# UI_Panel.net
KiCad netlist of a schematic drawn in Altium Designer
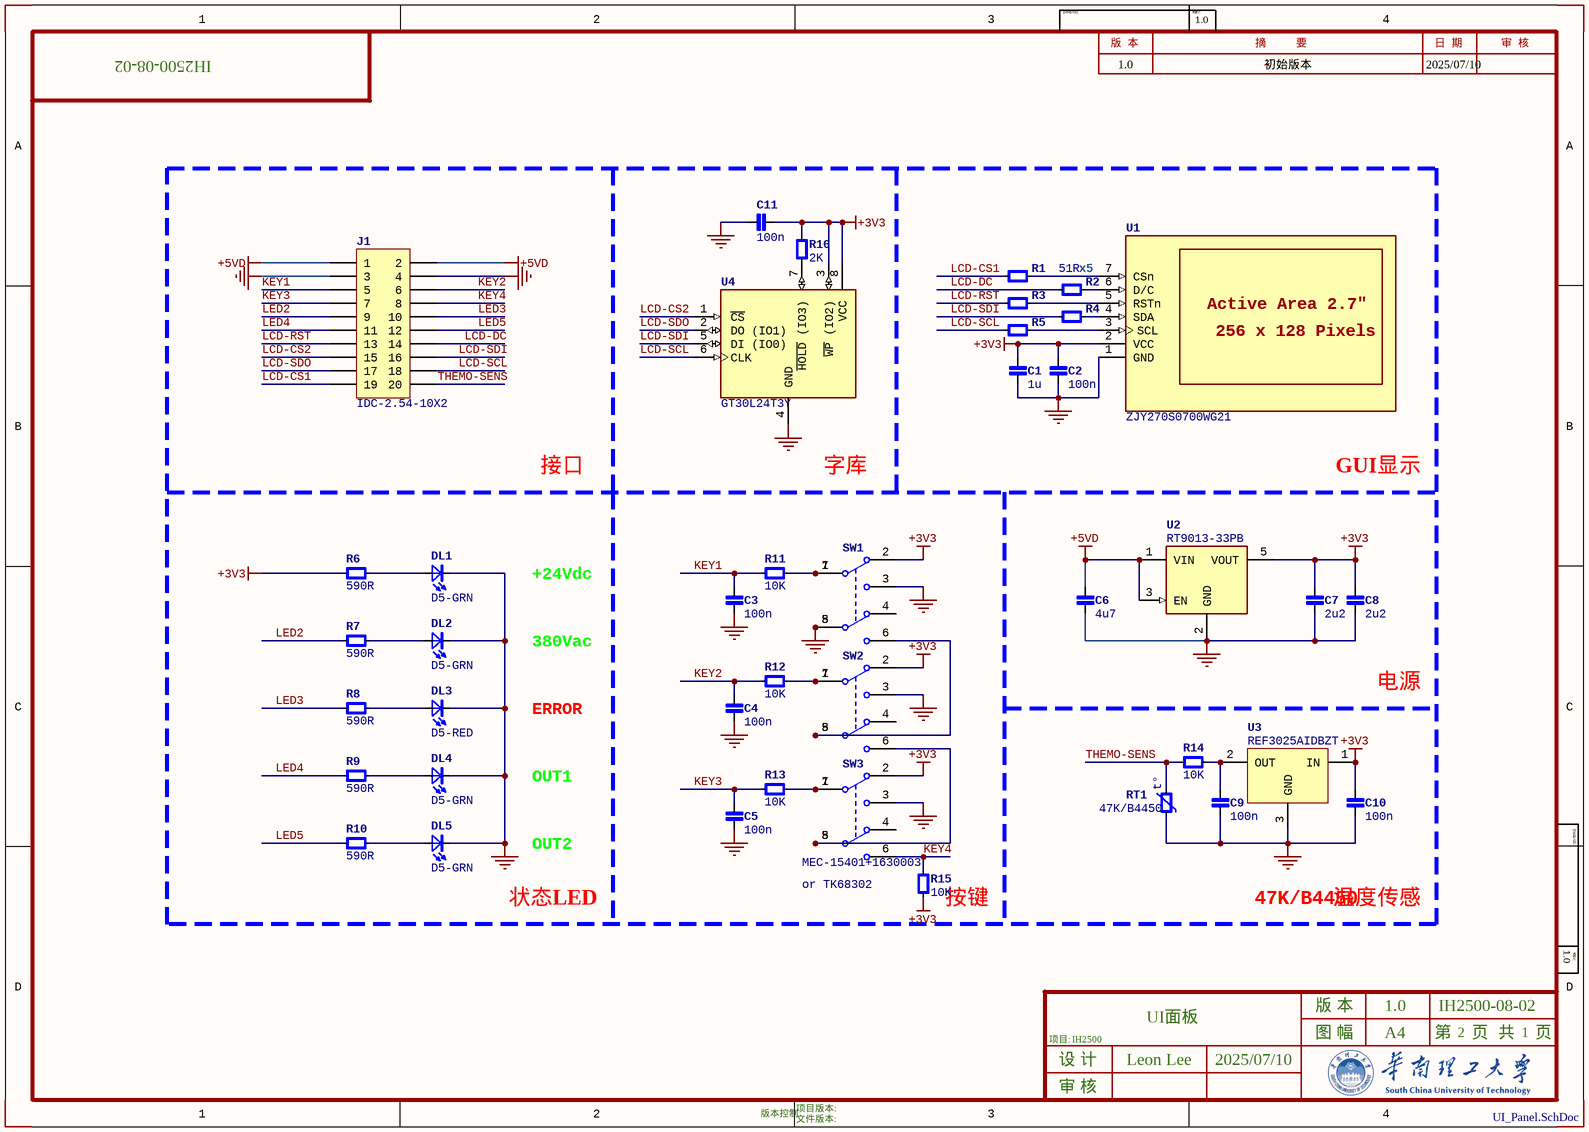
[diagram p0: UI_Panel.SchDoc]

(export (version "E")
  (design (tool "Eeschema 10.0.6"))
  (components
    (comp (ref "C1") (value "1u") (footprint "CAPC0805N") (libsource (lib "User_leo") (part "CAPACITOR(S)")))
    (comp (ref "C2")
      (value "100n")
      (footprint "CAPC0805N")
      (libsource (lib "User_leo") (part "CAPACITOR(S)"))
    )
    (comp (ref "C3")
      (value "100n")
      (footprint "CAPC0805N")
      (libsource (lib "User_leo") (part "CAPACITOR(S)"))
    )
    (comp (ref "C4")
      (value "100n")
      (footprint "CAPC0805N")
      (libsource (lib "User_leo") (part "CAPACITOR(S)"))
    )
    (comp (ref "C5")
      (value "100n")
      (footprint "CAPC0805N")
      (libsource (lib "User_leo") (part "CAPACITOR(S)"))
    )
    (comp (ref "C6") (value "4u7") (footprint "CAPC0805N") (libsource (lib "*") (part "CAPACITOR(S)")))
    (comp (ref "C7") (value "2u2") (footprint "CAPC0805N") (libsource (lib "User_leo") (part "CAPACITOR(S)")))
    (comp (ref "C8") (value "2u2") (footprint "CAPC0805N") (libsource (lib "User_leo") (part "CAPACITOR(S)")))
    (comp (ref "C9")
      (value "100n")
      (footprint "CAPC0805N")
      (libsource (lib "User_leo") (part "CAPACITOR(S)"))
    )
    (comp (ref "C10")
      (value "100n")
      (footprint "CAPC0805N")
      (libsource (lib "User_leo") (part "CAPACITOR(S)"))
    )
    (comp (ref "C11")
      (value "100n")
      (footprint "CAPC0805N")
      (libsource (lib "User_leo") (part "CAPACITOR(S)"))
    )
    (comp (ref "DL1")
      (value "D5-GRN")
      (footprint "LED-D5-GRN")
      (description "发光二极管")
      (libsource (lib "User_leo") (part "LED(S)"))
    )
    (comp (ref "DL2")
      (value "D5-GRN")
      (footprint "LED-D5-GRN")
      (description "发光二极管")
      (libsource (lib "User_leo") (part "LED(S)"))
    )
    (comp (ref "DL3")
      (value "D5-RED")
      (footprint "LED-D5-RED")
      (description "发光二极管")
      (libsource (lib "User_leo") (part "LED(S)"))
    )
    (comp (ref "DL4")
      (value "D5-GRN")
      (footprint "LED-D5-GRN")
      (description "发光二极管")
      (libsource (lib "User_leo") (part "LED(S)"))
    )
    (comp (ref "DL5")
      (value "D5-GRN")
      (footprint "LED-D5-GRN")
      (description "发光二极管")
      (libsource (lib "User_leo") (part "LED(S)"))
    )
    (comp (ref "J1")
      (value "IDC-2.54-10X2")
      (footprint "IDC2.54-V20A")
      (description "Header, 10-Pin, Dual row")
      (fields (field (name "PUBLISHER") "Altium Limited"))
      (libsource (lib "Miscellaneous Connectors") (part "Header 10X2"))
    )
    (comp (ref "R1")
      (value "51R")
      (footprint "RESC0805N")
      (description "电阻")
      (libsource (lib "User_leo") (part "RESISTOR(S)"))
    )
    (comp (ref "R2")
      (value "51R")
      (footprint "RESC0805N")
      (description "电阻")
      (libsource (lib "User_leo") (part "RESISTOR(S)"))
    )
    (comp (ref "R3")
      (value "51R")
      (footprint "RESC0805N")
      (description "电阻")
      (libsource (lib "User_leo") (part "RESISTOR(S)"))
    )
    (comp (ref "R4")
      (value "51R")
      (footprint "RESC0805N")
      (description "电阻")
      (libsource (lib "User_leo") (part "RESISTOR(S)"))
    )
    (comp (ref "R5")
      (value "51R")
      (footprint "RESC0805N")
      (description "电阻")
      (libsource (lib "User_leo") (part "RESISTOR(S)"))
    )
    (comp (ref "R6")
      (value "590R")
      (footprint "RESC0805N")
      (description "电阻")
      (libsource (lib "User_leo") (part "RESISTOR(S)"))
    )
    (comp (ref "R7")
      (value "590R")
      (footprint "RESC0805N")
      (description "电阻")
      (libsource (lib "User_leo") (part "RESISTOR(S)"))
    )
    (comp (ref "R8")
      (value "590R")
      (footprint "RESC0805N")
      (description "电阻")
      (libsource (lib "User_leo") (part "RESISTOR(S)"))
    )
    (comp (ref "R9")
      (value "590R")
      (footprint "RESC0805N")
      (description "电阻")
      (libsource (lib "User_leo") (part "RESISTOR(S)"))
    )
    (comp (ref "R10")
      (value "590R")
      (footprint "RESC0805N")
      (description "电阻")
      (libsource (lib "User_leo") (part "RESISTOR(S)"))
    )
    (comp (ref "R11")
      (value "10K")
      (footprint "RESC0805N")
      (description "电阻")
      (libsource (lib "User_leo") (part "RESISTOR(S)"))
    )
    (comp (ref "R12")
      (value "10K")
      (footprint "RESC0805N")
      (description "电阻")
      (libsource (lib "User_leo") (part "RESISTOR(S)"))
    )
    (comp (ref "R13")
      (value "10K")
      (footprint "RESC0805N")
      (description "电阻")
      (libsource (lib "User_leo") (part "RESISTOR(S)"))
    )
    (comp (ref "R14") (value "10K") (footprint "RESC0805N") (libsource (lib "*") (part "RESISTOR(S)")))
    (comp (ref "R15")
      (value "10K")
      (footprint "RESC0805N")
      (description "电阻")
      (libsource (lib "User_leo") (part "RESISTOR(S)"))
    )
    (comp (ref "R16") (value "2K") (footprint "RESC0805N") (libsource (lib "*") (part "RESISTOR(S)")))
    (comp (ref "RT1")
      (value "47K/B4450")
      (footprint "RESC0805N")
      (description "热敏电阻")
      (libsource (lib "User_leo") (part "RESISTOR(S) Thermal"))
    )
    (comp (ref "SW1")
      (value "MEC-15401+1630003")
      (footprint "SW-MEC-15xxx")
      (description "Switch")
      (fields (field (name "PUBLISHER") "Altium Limited"))
      (libsource (lib "Miscellaneous Devices") (part "SW DPDT"))
    )
    (comp (ref "SW2")
      (value "MEC-15401+1630003")
      (footprint "SW-MEC-15xxx")
      (description "Switch")
      (fields (field (name "PUBLISHER") "Altium Limited"))
      (libsource (lib "Miscellaneous Devices") (part "SW DPDT"))
    )
    (comp (ref "SW3")
      (value "MEC-15401+1630003")
      (footprint "SW-MEC-15xxx")
      (description "Switch")
      (fields (field (name "PUBLISHER") "Altium Limited"))
      (libsource (lib "Miscellaneous Devices") (part "SW DPDT"))
    )
    (comp (ref "U1")
      (value "ZJY270S0700WG21")
      (footprint "OLED-2.7-85x50")
      (description "中景园，ZJY270S0700YG21/WG21 OLED显示模组，256x128像素，16级灰度，SSD1363控制器，YG-黄色，WG-白色")
      (libsource (lib "User_leo") (part "OLED-ZJY270S0700"))
    )
    (comp (ref "U2")
      (value "RT9013-33PB")
      (footprint "SOT23-5_N")
      (description "500mA, Low Dropout, Low Noise Ultra-Fast Without Bypass Capacitor CMOS LDO Regulator")
      (libsource (lib "User_leo") (part "RT9013-xxPB"))
    )
    (comp (ref "U3")
      (value "REF3025AIDBZT")
      (footprint "DBZ0003A_N")
      (fields (field (name "MANUFACTURER") "Texas Instruments"))
      (libsource (lib "Altium Content Vault") (part "TI-REF3025DBZ3"))
    )
    (comp (ref "U4")
      (value "GT30L24T3Y")
      (footprint "SOP127P780-8N")
      (libsource (lib "User_leo") (part "WINB-W25Q40CL-SOIC-8"))
    )
  )
  (nets
    (net (code "1") (name "+3V3") (class "Default")
      (node (ref "C1") (pin "1") (pinfunction "1_1") (pintype "passive"))
      (node (ref "C10") (pin "1") (pinfunction "1_1") (pintype "passive"))
      (node (ref "C11") (pin "2") (pinfunction "2_2") (pintype "passive"))
      (node (ref "C2") (pin "1") (pinfunction "1_1") (pintype "passive"))
      (node (ref "C7") (pin "1") (pinfunction "1_1") (pintype "passive"))
      (node (ref "C8") (pin "1") (pinfunction "1_1") (pintype "passive"))
      (node (ref "R15") (pin "1") (pinfunction "1_1") (pintype "passive"))
      (node (ref "R16") (pin "1") (pinfunction "1_1") (pintype "passive"))
      (node (ref "R6") (pin "1") (pinfunction "1_1") (pintype "passive"))
      (node (ref "SW1") (pin "2") (pinfunction "NC1_2") (pintype "passive"))
      (node (ref "SW2") (pin "2") (pinfunction "NC1_2") (pintype "passive"))
      (node (ref "SW3") (pin "2") (pinfunction "NC1_2") (pintype "passive"))
      (node (ref "U1") (pin "2") (pinfunction "VCC_2") (pintype "power_in"))
      (node (ref "U2") (pin "5") (pinfunction "VOUT_5") (pintype "passive"))
      (node (ref "U3") (pin "1") (pinfunction "IN_1") (pintype "power_in"))
      (node (ref "U4") (pin "3") (pinfunction "~{WP}_(IO2)_3") (pintype "bidirectional"))
      (node (ref "U4") (pin "8") (pinfunction "VCC_8") (pintype "power_in"))
    )
    (net (code "2") (name "+5VD") (class "Default")
      (node (ref "C6") (pin "1") (pinfunction "1_1") (pintype "passive"))
      (node (ref "J1") (pin "1") (pinfunction "1_1") (pintype "passive"))
      (node (ref "J1") (pin "2") (pinfunction "2_2") (pintype "passive"))
      (node (ref "U2") (pin "1") (pinfunction "VIN_1") (pintype "passive"))
      (node (ref "U2") (pin "3") (pinfunction "EN_3") (pintype "input"))
    )
    (net (code "3") (name "/KEY1") (class "Default")
      (node (ref "C3") (pin "1") (pinfunction "1_1") (pintype "passive"))
      (node (ref "J1") (pin "5") (pinfunction "5_5") (pintype "passive"))
      (node (ref "R11") (pin "1") (pinfunction "1_1") (pintype "passive"))
    )
    (net (code "4") (name "/KEY2") (class "Default")
      (node (ref "C4") (pin "1") (pinfunction "1_1") (pintype "passive"))
      (node (ref "J1") (pin "6") (pinfunction "6_6") (pintype "passive"))
      (node (ref "R12") (pin "1") (pinfunction "1_1") (pintype "passive"))
    )
    (net (code "5") (name "/KEY3") (class "Default")
      (node (ref "C5") (pin "1") (pinfunction "1_1") (pintype "passive"))
      (node (ref "J1") (pin "7") (pinfunction "7_7") (pintype "passive"))
      (node (ref "R13") (pin "1") (pinfunction "1_1") (pintype "passive"))
    )
    (net (code "6") (name "/KEY4") (class "Default")
      (node (ref "J1") (pin "8") (pinfunction "8_8") (pintype "passive"))
      (node (ref "R15") (pin "2") (pinfunction "2_2") (pintype "passive"))
      (node (ref "SW3") (pin "6") (pinfunction "NO2_6") (pintype "passive"))
    )
    (net (code "7") (name "/LCD-CS1") (class "Default")
      (node (ref "J1") (pin "19") (pinfunction "19_19") (pintype "passive"))
      (node (ref "R1") (pin "1") (pinfunction "1_1") (pintype "passive"))
    )
    (net (code "8") (name "/LCD-CS2") (class "Default")
      (node (ref "J1") (pin "15") (pinfunction "15_15") (pintype "passive"))
      (node (ref "U4") (pin "1") (pinfunction "~{CS}_1") (pintype "input"))
    )
    (net (code "9") (name "/LCD-DC") (class "Default")
      (node (ref "J1") (pin "14") (pinfunction "14_14") (pintype "passive"))
      (node (ref "R2") (pin "1") (pinfunction "1_1") (pintype "passive"))
    )
    (net (code "10") (name "/LCD-RST") (class "Default")
      (node (ref "J1") (pin "13") (pinfunction "13_13") (pintype "passive"))
      (node (ref "R3") (pin "1") (pinfunction "1_1") (pintype "passive"))
    )
    (net (code "11") (name "/LCD-SCL") (class "Default")
      (node (ref "J1") (pin "18") (pinfunction "18_18") (pintype "passive"))
      (node (ref "R5") (pin "1") (pinfunction "1_1") (pintype "passive"))
      (node (ref "U4") (pin "6") (pinfunction "CLK_6") (pintype "input"))
    )
    (net (code "12") (name "/LCD-SDI") (class "Default")
      (node (ref "J1") (pin "16") (pinfunction "16_16") (pintype "passive"))
      (node (ref "R4") (pin "1") (pinfunction "1_1") (pintype "passive"))
      (node (ref "U4") (pin "5") (pinfunction "DI_(IO0)_5") (pintype "bidirectional"))
    )
    (net (code "13") (name "/LCD-SDO") (class "Default")
      (node (ref "J1") (pin "17") (pinfunction "17_17") (pintype "passive"))
      (node (ref "U4") (pin "2") (pinfunction "DO_(IO1)_2") (pintype "bidirectional"))
    )
    (net (code "14") (name "/LED2") (class "Default")
      (node (ref "J1") (pin "9") (pinfunction "9_9") (pintype "passive"))
      (node (ref "R7") (pin "1") (pinfunction "1_1") (pintype "passive"))
    )
    (net (code "15") (name "/LED3") (class "Default")
      (node (ref "J1") (pin "10") (pinfunction "10_10") (pintype "passive"))
      (node (ref "R8") (pin "1") (pinfunction "1_1") (pintype "passive"))
    )
    (net (code "16") (name "/LED4") (class "Default")
      (node (ref "J1") (pin "11") (pinfunction "11_11") (pintype "passive"))
      (node (ref "R9") (pin "1") (pinfunction "1_1") (pintype "passive"))
    )
    (net (code "17") (name "/LED5") (class "Default")
      (node (ref "J1") (pin "12") (pinfunction "12_12") (pintype "passive"))
      (node (ref "R10") (pin "1") (pinfunction "1_1") (pintype "passive"))
    )
    (net (code "18") (name "/THEMO-SENS") (class "Default")
      (node (ref "J1") (pin "20") (pinfunction "20_20") (pintype "passive"))
      (node (ref "R14") (pin "2") (pinfunction "2_2") (pintype "passive"))
      (node (ref "RT1") (pin "2") (pinfunction "2_2") (pintype "passive"))
    )
    (net (code "19") (name "GND") (class "Default")
      (node (ref "C1") (pin "2") (pinfunction "2_2") (pintype "passive"))
      (node (ref "C10") (pin "2") (pinfunction "2_2") (pintype "passive"))
      (node (ref "C11") (pin "1") (pinfunction "1_1") (pintype "passive"))
      (node (ref "C2") (pin "2") (pinfunction "2_2") (pintype "passive"))
      (node (ref "C3") (pin "2") (pinfunction "2_2") (pintype "passive"))
      (node (ref "C4") (pin "2") (pinfunction "2_2") (pintype "passive"))
      (node (ref "C5") (pin "2") (pinfunction "2_2") (pintype "passive"))
      (node (ref "C6") (pin "2") (pinfunction "2_2") (pintype "passive"))
      (node (ref "C7") (pin "2") (pinfunction "2_2") (pintype "passive"))
      (node (ref "C8") (pin "2") (pinfunction "2_2") (pintype "passive"))
      (node (ref "C9") (pin "2") (pinfunction "2_2") (pintype "passive"))
      (node (ref "DL1") (pin "2") (pinfunction "K_2") (pintype "passive"))
      (node (ref "DL2") (pin "2") (pinfunction "K_2") (pintype "passive"))
      (node (ref "DL3") (pin "2") (pinfunction "K_2") (pintype "passive"))
      (node (ref "DL4") (pin "2") (pinfunction "K_2") (pintype "passive"))
      (node (ref "DL5") (pin "2") (pinfunction "K_2") (pintype "passive"))
      (node (ref "J1") (pin "3") (pinfunction "3_3") (pintype "passive"))
      (node (ref "J1") (pin "4") (pinfunction "4_4") (pintype "passive"))
      (node (ref "RT1") (pin "1") (pinfunction "1_1") (pintype "passive"))
      (node (ref "SW1") (pin "3") (pinfunction "NO1_3") (pintype "passive"))
      (node (ref "SW1") (pin "5") (pinfunction "COMMON2_5") (pintype "passive"))
      (node (ref "SW1") (pin "8") (pinfunction "COM2_8") (pintype "passive"))
      (node (ref "SW2") (pin "3") (pinfunction "NO1_3") (pintype "passive"))
      (node (ref "SW3") (pin "3") (pinfunction "NO1_3") (pintype "passive"))
      (node (ref "U1") (pin "1") (pinfunction "GND_1") (pintype "power_in"))
      (node (ref "U2") (pin "2") (pinfunction "GND_2") (pintype "passive"))
      (node (ref "U3") (pin "3") (pinfunction "GND_3") (pintype "power_in"))
      (node (ref "U4") (pin "4") (pinfunction "GND_4") (pintype "power_in"))
    )
    (net (code "20") (name "Net-(DL1-A)") (class "Default")
      (node (ref "DL1") (pin "1") (pinfunction "A_1") (pintype "passive"))
      (node (ref "R6") (pin "2") (pinfunction "2_2") (pintype "passive"))
    )
    (net (code "21") (name "Net-(DL2-A)") (class "Default")
      (node (ref "DL2") (pin "1") (pinfunction "A_1") (pintype "passive"))
      (node (ref "R7") (pin "2") (pinfunction "2_2") (pintype "passive"))
    )
    (net (code "22") (name "Net-(DL3-A)") (class "Default")
      (node (ref "DL3") (pin "1") (pinfunction "A_1") (pintype "passive"))
      (node (ref "R8") (pin "2") (pinfunction "2_2") (pintype "passive"))
    )
    (net (code "23") (name "Net-(DL4-A)") (class "Default")
      (node (ref "DL4") (pin "1") (pinfunction "A_1") (pintype "passive"))
      (node (ref "R9") (pin "2") (pinfunction "2_2") (pintype "passive"))
    )
    (net (code "24") (name "Net-(DL5-A)") (class "Default")
      (node (ref "DL5") (pin "1") (pinfunction "A_1") (pintype "passive"))
      (node (ref "R10") (pin "2") (pinfunction "2_2") (pintype "passive"))
    )
    (net (code "25") (name "Net-(SW1-COM1)") (class "Default")
      (node (ref "R11") (pin "2") (pinfunction "2_2") (pintype "passive"))
      (node (ref "SW1") (pin "1") (pinfunction "COMMON1_1") (pintype "passive"))
      (node (ref "SW1") (pin "7") (pinfunction "COM1_7") (pintype "passive"))
    )
    (net (code "26") (name "Net-(SW1-NO2)") (class "Default")
      (node (ref "SW1") (pin "6") (pinfunction "NO2_6") (pintype "passive"))
      (node (ref "SW2") (pin "5") (pinfunction "COMMON2_5") (pintype "passive"))
      (node (ref "SW2") (pin "8") (pinfunction "COM2_8") (pintype "passive"))
    )
    (net (code "27") (name "Net-(SW2-COM1)") (class "Default")
      (node (ref "R12") (pin "2") (pinfunction "2_2") (pintype "passive"))
      (node (ref "SW2") (pin "1") (pinfunction "COMMON1_1") (pintype "passive"))
      (node (ref "SW2") (pin "7") (pinfunction "COM1_7") (pintype "passive"))
    )
    (net (code "28") (name "Net-(SW2-NO2)") (class "Default")
      (node (ref "SW2") (pin "6") (pinfunction "NO2_6") (pintype "passive"))
      (node (ref "SW3") (pin "5") (pinfunction "COMMON2_5") (pintype "passive"))
      (node (ref "SW3") (pin "8") (pinfunction "COM2_8") (pintype "passive"))
    )
    (net (code "29") (name "Net-(SW3-COM1)") (class "Default")
      (node (ref "R13") (pin "2") (pinfunction "2_2") (pintype "passive"))
      (node (ref "SW3") (pin "1") (pinfunction "COMMON1_1") (pintype "passive"))
      (node (ref "SW3") (pin "7") (pinfunction "COM1_7") (pintype "passive"))
    )
    (net (code "30") (name "Net-(U1-CSn)") (class "Default")
      (node (ref "R1") (pin "2") (pinfunction "2_2") (pintype "passive"))
      (node (ref "U1") (pin "7") (pinfunction "CSn_7") (pintype "input"))
    )
    (net (code "31") (name "Net-(U1-D{slash}C)") (class "Default")
      (node (ref "R2") (pin "2") (pinfunction "2_2") (pintype "passive"))
      (node (ref "U1") (pin "6") (pinfunction "D/C_6") (pintype "input"))
    )
    (net (code "32") (name "Net-(U1-RSTn)") (class "Default")
      (node (ref "R3") (pin "2") (pinfunction "2_2") (pintype "passive"))
      (node (ref "U1") (pin "5") (pinfunction "RSTn_5") (pintype "input"))
    )
    (net (code "33") (name "Net-(U1-SCL)") (class "Default")
      (node (ref "R5") (pin "2") (pinfunction "2_2") (pintype "passive"))
      (node (ref "U1") (pin "3") (pinfunction "SCL_3") (pintype "input"))
    )
    (net (code "34") (name "Net-(U1-SDA)") (class "Default")
      (node (ref "R4") (pin "2") (pinfunction "2_2") (pintype "passive"))
      (node (ref "U1") (pin "4") (pinfunction "SDA_4") (pintype "input"))
    )
    (net (code "35") (name "Net-(U3-OUT)") (class "Default")
      (node (ref "C9") (pin "1") (pinfunction "1_1") (pintype "passive"))
      (node (ref "R14") (pin "1") (pinfunction "1_1") (pintype "passive"))
      (node (ref "U3") (pin "2") (pinfunction "OUT_2") (pintype "power_in"))
    )
    (net (code "36") (name "Net-(U4-~{HOLD}_(IO3))") (class "Default")
      (node (ref "R16") (pin "2") (pinfunction "2_2") (pintype "passive"))
      (node (ref "U4") (pin "7") (pinfunction "~{HOLD}_(IO3)_7") (pintype "bidirectional"))
    )
    (net (code "37") (name "unconnected-(SW1-NC2-Pad4)") (class "Default")
      (node (ref "SW1") (pin "4") (pinfunction "NC2_4") (pintype "passive"))
    )
    (net (code "38") (name "unconnected-(SW2-NC2-Pad4)") (class "Default")
      (node (ref "SW2") (pin "4") (pinfunction "NC2_4") (pintype "passive"))
    )
    (net (code "39") (name "unconnected-(SW3-NC2-Pad4)") (class "Default")
      (node (ref "SW3") (pin "4") (pinfunction "NC2_4") (pintype "passive"))
    )
  )
)
